# Peripherals_-_Servos.net
KiCad netlist of a schematic drawn in Altium Designer
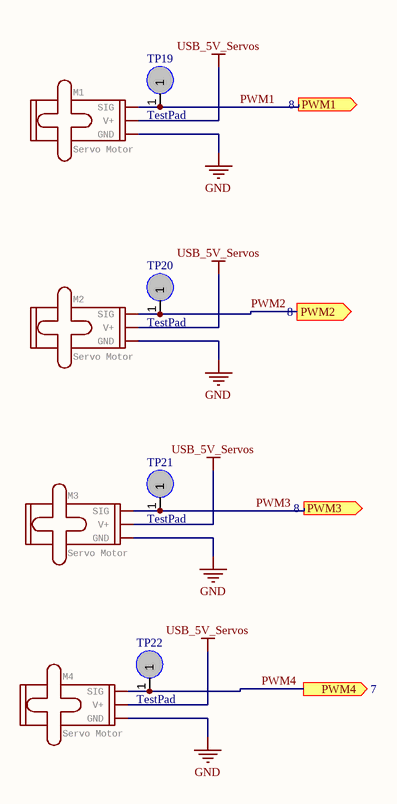
[diagram p0: Peripherals - Servos.SchDoc]

(export (version "E")
  (design (tool "Eeschema 10.0.6"))
  (components
    (comp (ref "M1")
      (value "Servo Motor")
      (footprint "1X03")
      (libsource (lib "SparkFun-Electromechanical.Library") (part "SERVO"))
    )
    (comp (ref "M2")
      (value "Servo Motor")
      (footprint "1X03")
      (libsource (lib "SparkFun-Electromechanical.Library") (part "SERVO"))
    )
    (comp (ref "M3")
      (value "Servo Motor")
      (footprint "1X03")
      (libsource (lib "SparkFun-Electromechanical.Library") (part "SERVO"))
    )
    (comp (ref "M4")
      (value "Servo Motor")
      (footprint "1X03")
      (libsource (lib "SparkFun-Electromechanical.Library") (part "SERVO"))
    )
    (comp (ref "TP19")
      (value "TestPad")
      (footprint "TestPad50mil")
      (libsource (lib "SchemSymbolsGoogle") (part "TestPad"))
    )
    (comp (ref "TP20")
      (value "TestPad")
      (footprint "TestPad50mil")
      (libsource (lib "SchemSymbolsGoogle") (part "TestPad"))
    )
    (comp (ref "TP21")
      (value "TestPad")
      (footprint "TestPad50mil")
      (libsource (lib "SchemSymbolsGoogle") (part "TestPad"))
    )
    (comp (ref "TP22")
      (value "TestPad")
      (footprint "TestPad50mil")
      (libsource (lib "SchemSymbolsGoogle") (part "TestPad"))
    )
  )
  (nets
    (net (code "1") (name "/PWM1") (class "Default")
      (node (ref "M1") (pin "1") (pinfunction "SIG_1") (pintype "bidirectional"))
      (node (ref "TP19") (pin "1") (pinfunction "1_1") (pintype "passive"))
    )
    (net (code "2") (name "/PWM2") (class "Default")
      (node (ref "M2") (pin "1") (pinfunction "SIG_1") (pintype "bidirectional"))
      (node (ref "TP20") (pin "1") (pinfunction "1_1") (pintype "passive"))
    )
    (net (code "3") (name "/PWM3") (class "Default")
      (node (ref "M3") (pin "1") (pinfunction "SIG_1") (pintype "bidirectional"))
      (node (ref "TP21") (pin "1") (pinfunction "1_1") (pintype "passive"))
    )
    (net (code "4") (name "/PWM4") (class "Default")
      (node (ref "M4") (pin "1") (pinfunction "SIG_1") (pintype "bidirectional"))
      (node (ref "TP22") (pin "1") (pinfunction "1_1") (pintype "passive"))
    )
    (net (code "5") (name "GND") (class "Default")
      (node (ref "M1") (pin "3") (pinfunction "GND_3") (pintype "bidirectional"))
      (node (ref "M2") (pin "3") (pinfunction "GND_3") (pintype "bidirectional"))
      (node (ref "M3") (pin "3") (pinfunction "GND_3") (pintype "bidirectional"))
      (node (ref "M4") (pin "3") (pinfunction "GND_3") (pintype "bidirectional"))
    )
    (net (code "6") (name "USB_5V_Servos") (class "Default")
      (node (ref "M1") (pin "2") (pinfunction "V+_2") (pintype "bidirectional"))
      (node (ref "M2") (pin "2") (pinfunction "V+_2") (pintype "bidirectional"))
      (node (ref "M3") (pin "2") (pinfunction "V+_2") (pintype "bidirectional"))
      (node (ref "M4") (pin "2") (pinfunction "V+_2") (pintype "bidirectional"))
    )
  )
)
